# 13_-LED_INDICATION.net
KiCad netlist of a schematic drawn in Altium Designer
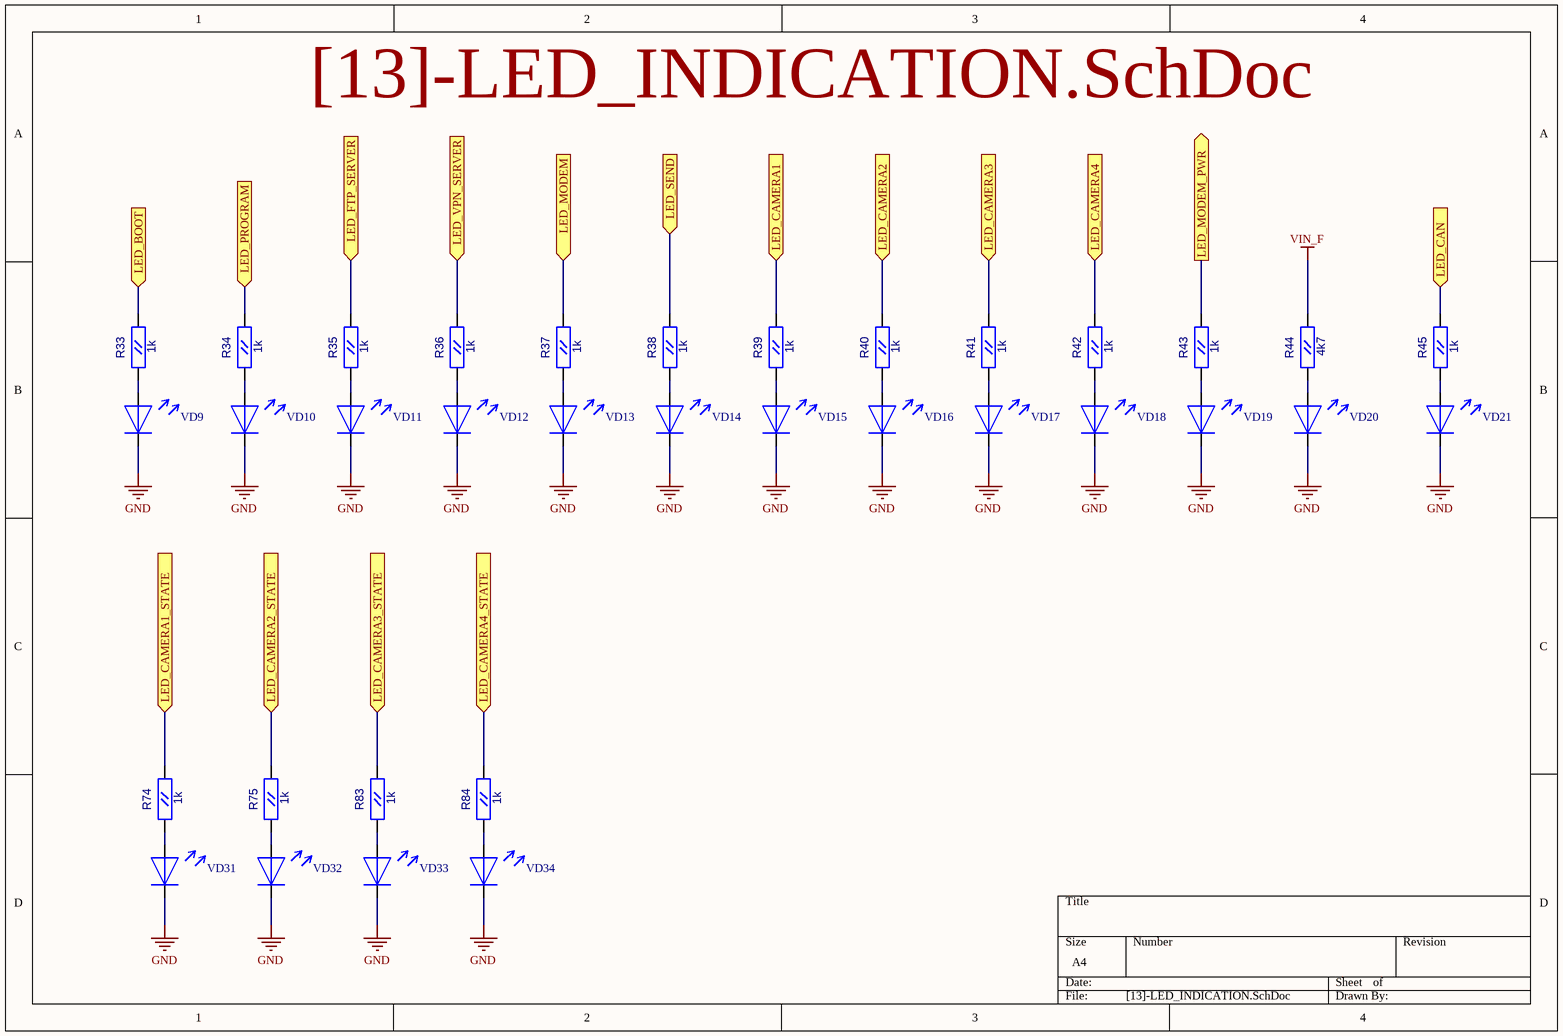
[diagram p0: [13]-LED_INDICATION.SchDoc]

(export (version "E")
  (design (tool "Eeschema 10.0.6"))
  (components
    (comp (ref "R33")
      (value "1k")
      (footprint "RC0603")
      (description "RC0603")
      (libsource (lib "gprs_modem_2") (part "RC0603"))
    )
    (comp (ref "R34")
      (value "1k")
      (footprint "RC0603")
      (description "RC0603")
      (libsource (lib "gprs_modem_2") (part "RC0603"))
    )
    (comp (ref "R35")
      (value "1k")
      (footprint "RC0603")
      (description "RC0603")
      (libsource (lib "gprs_modem_2") (part "RC0603"))
    )
    (comp (ref "R36")
      (value "1k")
      (footprint "RC0603")
      (description "RC0603")
      (libsource (lib "gprs_modem_2") (part "RC0603"))
    )
    (comp (ref "R37")
      (value "1k")
      (footprint "RC0603")
      (description "RC0603")
      (libsource (lib "gprs_modem_2") (part "RC0603"))
    )
    (comp (ref "R38")
      (value "1k")
      (footprint "RC0603")
      (description "RC0603")
      (libsource (lib "gprs_modem_2") (part "RC0603"))
    )
    (comp (ref "R39")
      (value "1k")
      (footprint "RC0603")
      (description "RC0603")
      (libsource (lib "gprs_modem_2") (part "RC0603"))
    )
    (comp (ref "R40")
      (value "1k")
      (footprint "RC0603")
      (description "RC0603")
      (libsource (lib "gprs_modem_2") (part "RC0603"))
    )
    (comp (ref "R41")
      (value "1k")
      (footprint "RC0603")
      (description "RC0603")
      (libsource (lib "gprs_modem_2") (part "RC0603"))
    )
    (comp (ref "R42")
      (value "1k")
      (footprint "RC0603")
      (description "RC0603")
      (libsource (lib "gprs_modem_2") (part "RC0603"))
    )
    (comp (ref "R43")
      (value "1k")
      (footprint "RC0603")
      (description "RC0603")
      (libsource (lib "gprs_modem_2") (part "RC0603"))
    )
    (comp (ref "R44")
      (value "4k7")
      (footprint "RC0603")
      (description "RC0603")
      (libsource (lib "gprs_modem_2") (part "RC0603"))
    )
    (comp (ref "R45")
      (value "1k")
      (footprint "RC0603")
      (description "RC0603")
      (libsource (lib "gprs_modem_2") (part "RC0603"))
    )
    (comp (ref "R74")
      (value "1k")
      (footprint "RC0603")
      (description "RC0603")
      (libsource (lib "gprs_modem_2") (part "RC0603"))
    )
    (comp (ref "R75")
      (value "1k")
      (footprint "RC0603")
      (description "RC0603")
      (libsource (lib "gprs_modem_2") (part "RC0603"))
    )
    (comp (ref "R83")
      (value "1k")
      (footprint "RC0603")
      (description "RC0603")
      (libsource (lib "gprs_modem_2") (part "RC0603"))
    )
    (comp (ref "R84")
      (value "1k")
      (footprint "RC0603")
      (description "RC0603")
      (libsource (lib "gprs_modem_2") (part "RC0603"))
    )
    (comp (ref "VD9")
      (value "LED_0805")
      (footprint "LED0805")
      (libsource (lib "gprs_modem_2") (part "LED_0805"))
    )
    (comp (ref "VD10")
      (value "LED_0805")
      (footprint "LED0805")
      (libsource (lib "gprs_modem_2") (part "LED_0805"))
    )
    (comp (ref "VD11")
      (value "LED_0805")
      (footprint "LED0805")
      (libsource (lib "gprs_modem_2") (part "LED_0805"))
    )
    (comp (ref "VD12")
      (value "LED_0805")
      (footprint "LED0805")
      (libsource (lib "gprs_modem_2") (part "LED_0805"))
    )
    (comp (ref "VD13")
      (value "LED_0805")
      (footprint "LED0805")
      (libsource (lib "gprs_modem_2") (part "LED_0805"))
    )
    (comp (ref "VD14")
      (value "LED_0805")
      (footprint "LED0805")
      (libsource (lib "gprs_modem_2") (part "LED_0805"))
    )
    (comp (ref "VD15")
      (value "LED_0805")
      (footprint "LED0805")
      (libsource (lib "gprs_modem_2") (part "LED_0805"))
    )
    (comp (ref "VD16")
      (value "LED_0805")
      (footprint "LED0805")
      (libsource (lib "gprs_modem_2") (part "LED_0805"))
    )
    (comp (ref "VD17")
      (value "LED_0805")
      (footprint "LED0805")
      (libsource (lib "gprs_modem_2") (part "LED_0805"))
    )
    (comp (ref "VD18")
      (value "LED_0805")
      (footprint "LED0805")
      (libsource (lib "gprs_modem_2") (part "LED_0805"))
    )
    (comp (ref "VD19")
      (value "LED_0805")
      (footprint "LED0805")
      (libsource (lib "gprs_modem_2") (part "LED_0805"))
    )
    (comp (ref "VD20")
      (value "LED_0805")
      (footprint "LED0805")
      (libsource (lib "gprs_modem_2") (part "LED_0805"))
    )
    (comp (ref "VD21")
      (value "LED_0805")
      (footprint "LED0805")
      (libsource (lib "gprs_modem_2") (part "LED_0805"))
    )
    (comp (ref "VD31")
      (value "LED_0805")
      (footprint "LED0805")
      (libsource (lib "gprs_modem_2") (part "LED_0805"))
    )
    (comp (ref "VD32")
      (value "LED_0805")
      (footprint "LED0805")
      (libsource (lib "gprs_modem_2") (part "LED_0805"))
    )
    (comp (ref "VD33")
      (value "LED_0805")
      (footprint "LED0805")
      (libsource (lib "gprs_modem_2") (part "LED_0805"))
    )
    (comp (ref "VD34")
      (value "LED_0805")
      (footprint "LED0805")
      (libsource (lib "gprs_modem_2") (part "LED_0805"))
    )
  )
  (nets
    (net (code "1") (name "/LED_BOOT") (class "Default")
      (node (ref "R33") (pin "2") (pinfunction "B_2") (pintype "passive"))
    )
    (net (code "2") (name "/LED_CAMERA1") (class "Default")
      (node (ref "R39") (pin "2") (pinfunction "B_2") (pintype "passive"))
    )
    (net (code "3") (name "/LED_CAMERA1_STATE") (class "Default")
      (node (ref "R74") (pin "2") (pinfunction "B_2") (pintype "passive"))
    )
    (net (code "4") (name "/LED_CAMERA2") (class "Default")
      (node (ref "R40") (pin "2") (pinfunction "B_2") (pintype "passive"))
    )
    (net (code "5") (name "/LED_CAMERA2_STATE") (class "Default")
      (node (ref "R75") (pin "2") (pinfunction "B_2") (pintype "passive"))
    )
    (net (code "6") (name "/LED_CAMERA3") (class "Default")
      (node (ref "R41") (pin "2") (pinfunction "B_2") (pintype "passive"))
    )
    (net (code "7") (name "/LED_CAMERA3_STATE") (class "Default")
      (node (ref "R83") (pin "2") (pinfunction "B_2") (pintype "passive"))
    )
    (net (code "8") (name "/LED_CAMERA4") (class "Default")
      (node (ref "R42") (pin "2") (pinfunction "B_2") (pintype "passive"))
    )
    (net (code "9") (name "/LED_CAMERA4_STATE") (class "Default")
      (node (ref "R84") (pin "2") (pinfunction "B_2") (pintype "passive"))
    )
    (net (code "10") (name "/LED_CAN") (class "Default")
      (node (ref "R45") (pin "2") (pinfunction "B_2") (pintype "passive"))
    )
    (net (code "11") (name "/LED_FTP_SERVER") (class "Default")
      (node (ref "R35") (pin "2") (pinfunction "B_2") (pintype "passive"))
    )
    (net (code "12") (name "/LED_MODEM") (class "Default")
      (node (ref "R37") (pin "2") (pinfunction "B_2") (pintype "passive"))
    )
    (net (code "13") (name "/LED_MODEM_PWR") (class "Default")
      (node (ref "R43") (pin "2") (pinfunction "B_2") (pintype "passive"))
    )
    (net (code "14") (name "/LED_PROGRAM") (class "Default")
      (node (ref "R34") (pin "2") (pinfunction "B_2") (pintype "passive"))
    )
    (net (code "15") (name "/LED_SEND") (class "Default")
      (node (ref "R38") (pin "2") (pinfunction "B_2") (pintype "passive"))
    )
    (net (code "16") (name "/LED_VPN_SERVER") (class "Default")
      (node (ref "R36") (pin "2") (pinfunction "B_2") (pintype "passive"))
    )
    (net (code "17") (name "GND") (class "Default")
      (node (ref "VD10") (pin "2") (pintype "passive"))
      (node (ref "VD11") (pin "2") (pintype "passive"))
      (node (ref "VD12") (pin "2") (pintype "passive"))
      (node (ref "VD13") (pin "2") (pintype "passive"))
      (node (ref "VD14") (pin "2") (pintype "passive"))
      (node (ref "VD15") (pin "2") (pintype "passive"))
      (node (ref "VD16") (pin "2") (pintype "passive"))
      (node (ref "VD17") (pin "2") (pintype "passive"))
      (node (ref "VD18") (pin "2") (pintype "passive"))
      (node (ref "VD19") (pin "2") (pintype "passive"))
      (node (ref "VD20") (pin "2") (pintype "passive"))
      (node (ref "VD21") (pin "2") (pintype "passive"))
      (node (ref "VD31") (pin "2") (pintype "passive"))
      (node (ref "VD32") (pin "2") (pintype "passive"))
      (node (ref "VD33") (pin "2") (pintype "passive"))
      (node (ref "VD34") (pin "2") (pintype "passive"))
      (node (ref "VD9") (pin "2") (pintype "passive"))
    )
    (net (code "18") (name "Net-(R33-A)") (class "Default")
      (node (ref "R33") (pin "1") (pinfunction "A_1") (pintype "passive"))
      (node (ref "VD9") (pin "1") (pintype "passive"))
    )
    (net (code "19") (name "Net-(R34-A)") (class "Default")
      (node (ref "R34") (pin "1") (pinfunction "A_1") (pintype "passive"))
      (node (ref "VD10") (pin "1") (pintype "passive"))
    )
    (net (code "20") (name "Net-(R35-A)") (class "Default")
      (node (ref "R35") (pin "1") (pinfunction "A_1") (pintype "passive"))
      (node (ref "VD11") (pin "1") (pintype "passive"))
    )
    (net (code "21") (name "Net-(R36-A)") (class "Default")
      (node (ref "R36") (pin "1") (pinfunction "A_1") (pintype "passive"))
      (node (ref "VD12") (pin "1") (pintype "passive"))
    )
    (net (code "22") (name "Net-(R37-A)") (class "Default")
      (node (ref "R37") (pin "1") (pinfunction "A_1") (pintype "passive"))
      (node (ref "VD13") (pin "1") (pintype "passive"))
    )
    (net (code "23") (name "Net-(R38-A)") (class "Default")
      (node (ref "R38") (pin "1") (pinfunction "A_1") (pintype "passive"))
      (node (ref "VD14") (pin "1") (pintype "passive"))
    )
    (net (code "24") (name "Net-(R39-A)") (class "Default")
      (node (ref "R39") (pin "1") (pinfunction "A_1") (pintype "passive"))
      (node (ref "VD15") (pin "1") (pintype "passive"))
    )
    (net (code "25") (name "Net-(R40-A)") (class "Default")
      (node (ref "R40") (pin "1") (pinfunction "A_1") (pintype "passive"))
      (node (ref "VD16") (pin "1") (pintype "passive"))
    )
    (net (code "26") (name "Net-(R41-A)") (class "Default")
      (node (ref "R41") (pin "1") (pinfunction "A_1") (pintype "passive"))
      (node (ref "VD17") (pin "1") (pintype "passive"))
    )
    (net (code "27") (name "Net-(R42-A)") (class "Default")
      (node (ref "R42") (pin "1") (pinfunction "A_1") (pintype "passive"))
      (node (ref "VD18") (pin "1") (pintype "passive"))
    )
    (net (code "28") (name "Net-(R43-A)") (class "Default")
      (node (ref "R43") (pin "1") (pinfunction "A_1") (pintype "passive"))
      (node (ref "VD19") (pin "1") (pintype "passive"))
    )
    (net (code "29") (name "Net-(R44-A)") (class "Default")
      (node (ref "R44") (pin "1") (pinfunction "A_1") (pintype "passive"))
      (node (ref "VD20") (pin "1") (pintype "passive"))
    )
    (net (code "30") (name "Net-(R45-A)") (class "Default")
      (node (ref "R45") (pin "1") (pinfunction "A_1") (pintype "passive"))
      (node (ref "VD21") (pin "1") (pintype "passive"))
    )
    (net (code "31") (name "Net-(R74-A)") (class "Default")
      (node (ref "R74") (pin "1") (pinfunction "A_1") (pintype "passive"))
      (node (ref "VD31") (pin "1") (pintype "passive"))
    )
    (net (code "32") (name "Net-(R75-A)") (class "Default")
      (node (ref "R75") (pin "1") (pinfunction "A_1") (pintype "passive"))
      (node (ref "VD32") (pin "1") (pintype "passive"))
    )
    (net (code "33") (name "Net-(R83-A)") (class "Default")
      (node (ref "R83") (pin "1") (pinfunction "A_1") (pintype "passive"))
      (node (ref "VD33") (pin "1") (pintype "passive"))
    )
    (net (code "34") (name "Net-(R84-A)") (class "Default")
      (node (ref "R84") (pin "1") (pinfunction "A_1") (pintype "passive"))
      (node (ref "VD34") (pin "1") (pintype "passive"))
    )
    (net (code "35") (name "VIN_F") (class "Default")
      (node (ref "R44") (pin "2") (pinfunction "B_2") (pintype "passive"))
    )
  )
)
